# ge7.net
KiCad netlist of a schematic drawn in EAGLE
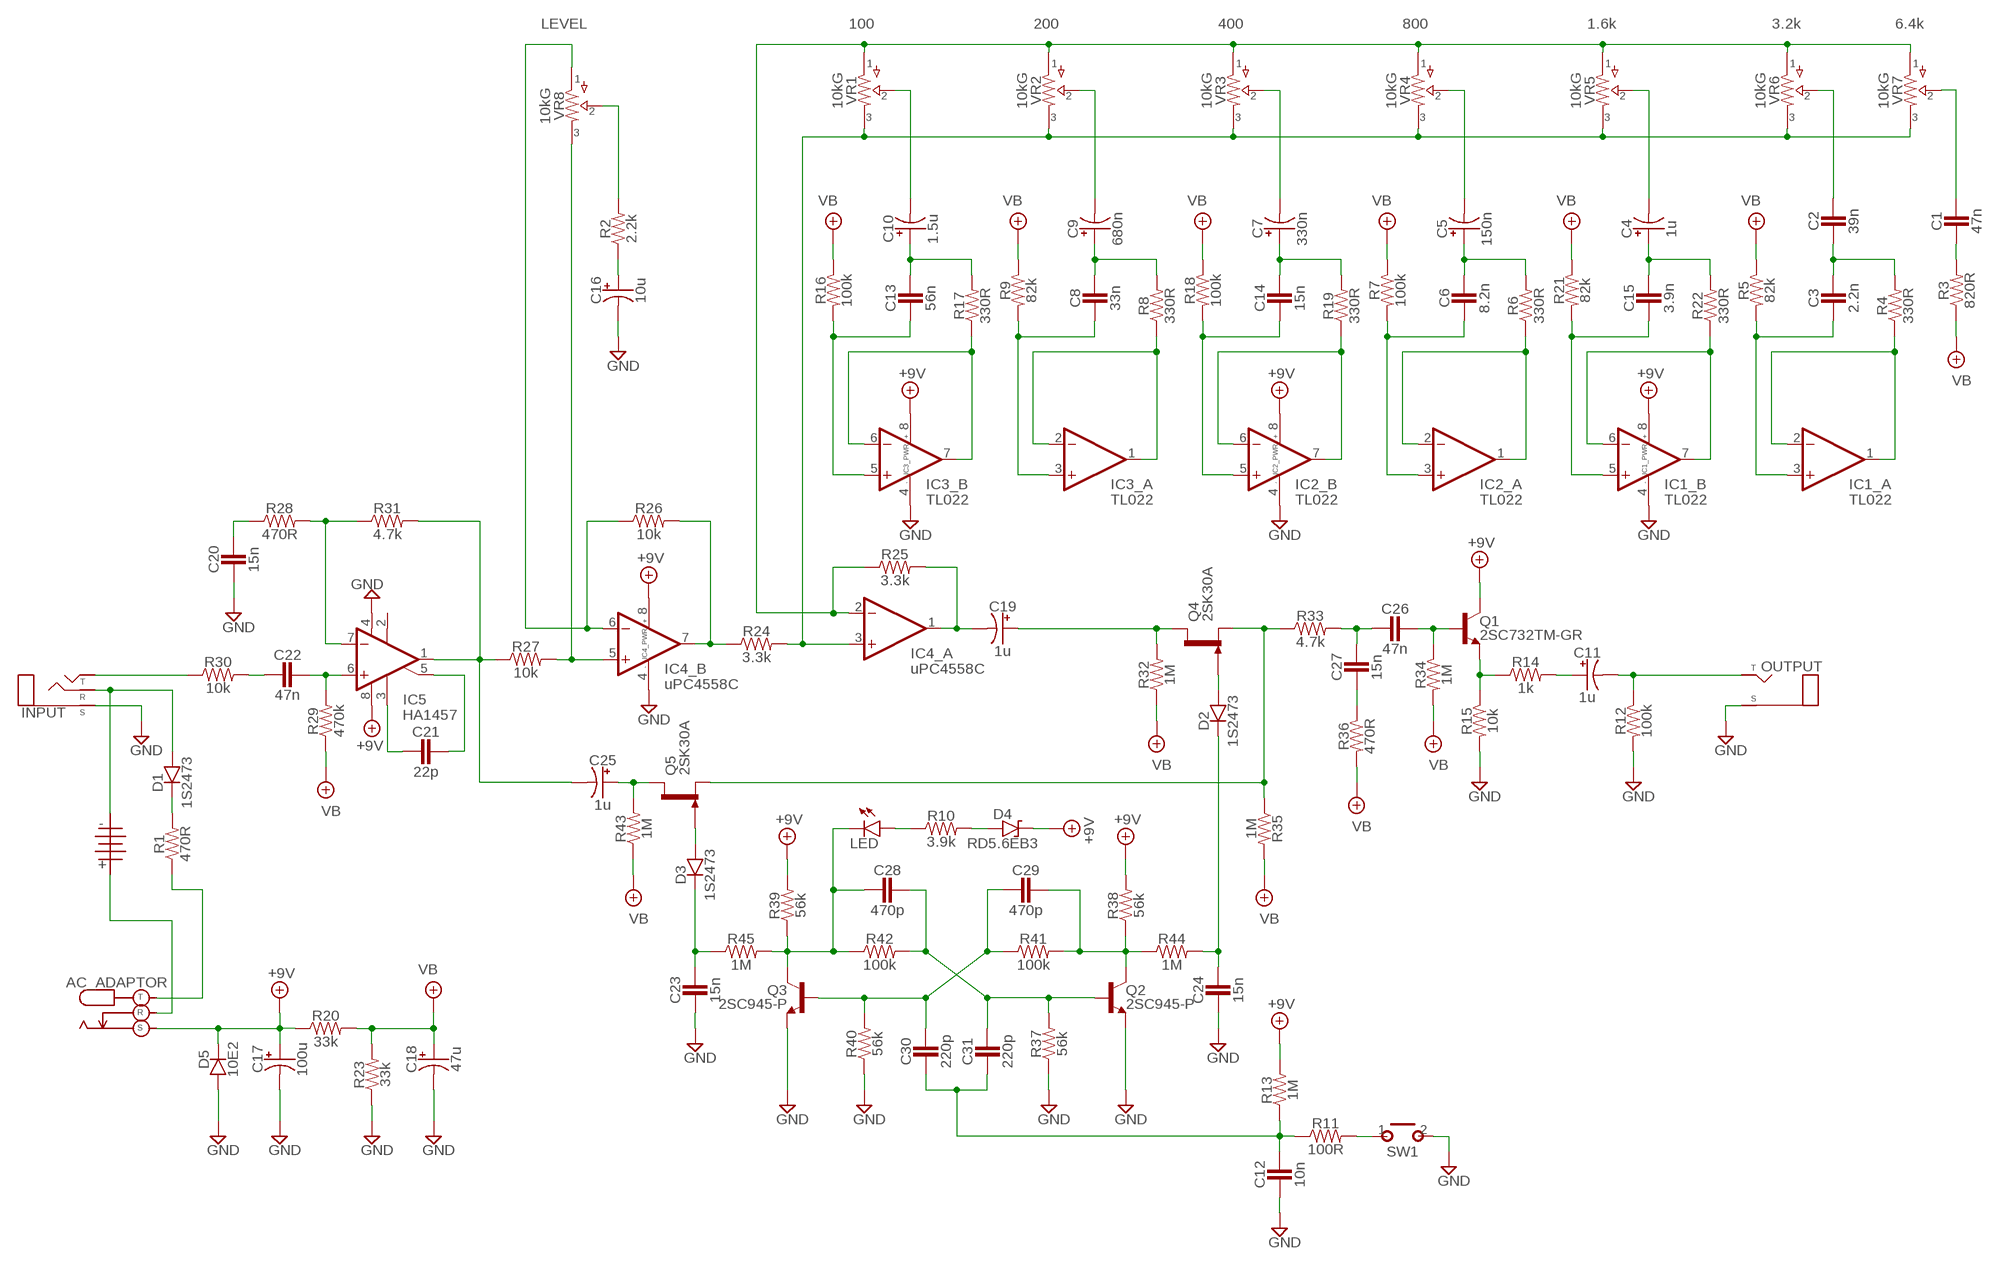
[diagram p0: schematic, sheet 1]

(export (version "E")
  (design (tool "Eeschema 10.0.6"))
  (components
    (comp (ref "AC_ADAPTOR")
      (value "DC_KOBICONN")
      (footprint "eagle-import:DC_KOBICONN")
      (libsource (lib "eagle-import") (part "DC_KOBICONN"))
    )
    (comp (ref "BATTERY")
      (value "BATTERY")
      (footprint "eagle-import:TWO_PADS")
      (libsource (lib "eagle-import") (part "BATTERY"))
    )
    (comp (ref "C1")
      (value "47n")
      (footprint "eagle-import:BOX_SMALL")
      (libsource (lib "eagle-import") (part "CER/FILMBOX.1"))
    )
    (comp (ref "C2")
      (value "39n")
      (footprint "eagle-import:BOX_SMALL")
      (libsource (lib "eagle-import") (part "CER/FILMBOX.1"))
    )
    (comp (ref "C3")
      (value "2.2n")
      (footprint "eagle-import:BOX_SMALL")
      (libsource (lib "eagle-import") (part "CER/FILMBOX.1"))
    )
    (comp (ref "C4")
      (value "1u")
      (footprint "eagle-import:040_020")
      (libsource (lib "eagle-import") (part "0400"))
    )
    (comp (ref "C5")
      (value "150n")
      (footprint "eagle-import:040_020")
      (libsource (lib "eagle-import") (part "0400"))
    )
    (comp (ref "C6")
      (value "8.2n")
      (footprint "eagle-import:BOX_SMALL")
      (libsource (lib "eagle-import") (part "CER/FILMBOX.1"))
    )
    (comp (ref "C7")
      (value "330n")
      (footprint "eagle-import:040_020")
      (libsource (lib "eagle-import") (part "0400"))
    )
    (comp (ref "C8")
      (value "33n")
      (footprint "eagle-import:BOX_SMALL")
      (libsource (lib "eagle-import") (part "CER/FILMBOX.1"))
    )
    (comp (ref "C9")
      (value "680n")
      (footprint "eagle-import:040_020")
      (libsource (lib "eagle-import") (part "0400"))
    )
    (comp (ref "C10")
      (value "1.5u")
      (footprint "eagle-import:040_020")
      (libsource (lib "eagle-import") (part "0400"))
    )
    (comp (ref "C11")
      (value "1u")
      (footprint "eagle-import:040_020")
      (libsource (lib "eagle-import") (part "0400"))
    )
    (comp (ref "C12")
      (value "10n")
      (footprint "eagle-import:BOX_SMALL")
      (libsource (lib "eagle-import") (part "CER/FILMBOX.1"))
    )
    (comp (ref "C13")
      (value "56n")
      (footprint "eagle-import:BOX_SMALL")
      (libsource (lib "eagle-import") (part "CER/FILMBOX.1"))
    )
    (comp (ref "C14")
      (value "15n")
      (footprint "eagle-import:BOX_SMALL")
      (libsource (lib "eagle-import") (part "CER/FILMBOX.1"))
    )
    (comp (ref "C15")
      (value "3.9n")
      (footprint "eagle-import:BOX_SMALL")
      (libsource (lib "eagle-import") (part "CER/FILMBOX.1"))
    )
    (comp (ref "C16")
      (value "10u")
      (footprint "eagle-import:040_020")
      (libsource (lib "eagle-import") (part "0400"))
    )
    (comp (ref "C17")
      (value "100u")
      (footprint "eagle-import:040_020")
      (libsource (lib "eagle-import") (part "0400"))
    )
    (comp (ref "C18")
      (value "47u")
      (footprint "eagle-import:040_020")
      (libsource (lib "eagle-import") (part "0400"))
    )
    (comp (ref "C19")
      (value "1u")
      (footprint "eagle-import:040_020")
      (libsource (lib "eagle-import") (part "0400"))
    )
    (comp (ref "C20")
      (value "15n")
      (footprint "eagle-import:BOX_SMALL")
      (libsource (lib "eagle-import") (part "CER/FILMBOX.1"))
    )
    (comp (ref "C21")
      (value "22p")
      (footprint "eagle-import:BOX_SMALL")
      (libsource (lib "eagle-import") (part "CER/FILMBOX.1"))
    )
    (comp (ref "C22")
      (value "47n")
      (footprint "eagle-import:BOX_SMALL")
      (libsource (lib "eagle-import") (part "CER/FILMBOX.1"))
    )
    (comp (ref "C23")
      (value "15n")
      (footprint "eagle-import:BOX_SMALL")
      (libsource (lib "eagle-import") (part "CER/FILMBOX.1"))
    )
    (comp (ref "C24")
      (value "15n")
      (footprint "eagle-import:BOX_SMALL")
      (libsource (lib "eagle-import") (part "CER/FILMBOX.1"))
    )
    (comp (ref "C25")
      (value "1u")
      (footprint "eagle-import:040_020")
      (libsource (lib "eagle-import") (part "0400"))
    )
    (comp (ref "C26")
      (value "47n")
      (footprint "eagle-import:BOX_SMALL")
      (libsource (lib "eagle-import") (part "CER/FILMBOX.1"))
    )
    (comp (ref "C27")
      (value "15n")
      (footprint "eagle-import:BOX_SMALL")
      (libsource (lib "eagle-import") (part "CER/FILMBOX.1"))
    )
    (comp (ref "C28")
      (value "470p")
      (footprint "eagle-import:BOX_SMALL")
      (libsource (lib "eagle-import") (part "CER/FILMBOX.1"))
    )
    (comp (ref "C29")
      (value "470p")
      (footprint "eagle-import:BOX_SMALL")
      (libsource (lib "eagle-import") (part "CER/FILMBOX.1"))
    )
    (comp (ref "C30")
      (value "220p")
      (footprint "eagle-import:BOX_SMALL")
      (libsource (lib "eagle-import") (part "CER/FILMBOX.1"))
    )
    (comp (ref "C31")
      (value "220p")
      (footprint "eagle-import:BOX_SMALL")
      (libsource (lib "eagle-import") (part "CER/FILMBOX.1"))
    )
    (comp (ref "D1")
      (value "1S2473")
      (footprint "eagle-import:DO35-2")
      (libsource (lib "eagle-import") (part "DO35.2"))
    )
    (comp (ref "D2")
      (value "1S2473")
      (footprint "eagle-import:DO35-2")
      (libsource (lib "eagle-import") (part "DO35.2"))
    )
    (comp (ref "D3")
      (value "1S2473")
      (footprint "eagle-import:DO35-2")
      (libsource (lib "eagle-import") (part "DO35.2"))
    )
    (comp (ref "D4")
      (value "RD5.6EB3")
      (footprint "eagle-import:DO41-2")
      (libsource (lib "eagle-import") (part "ZENER.2"))
    )
    (comp (ref "D5")
      (value "10E2")
      (footprint "eagle-import:DO35-2")
      (libsource (lib "eagle-import") (part "DO35.2"))
    )
    (comp (ref "IC1")
      (value "TL022")
      (footprint "eagle-import:DIL0")
      (libsource (lib "eagle-import") (part "DUALTH"))
    )
    (comp (ref "IC2")
      (value "TL022")
      (footprint "eagle-import:DIL0")
      (libsource (lib "eagle-import") (part "DUALTH"))
    )
    (comp (ref "IC3")
      (value "TL022")
      (footprint "eagle-import:DIL0")
      (libsource (lib "eagle-import") (part "DUALTH"))
    )
    (comp (ref "IC4")
      (value "uPC4558C")
      (footprint "eagle-import:DIL0")
      (libsource (lib "eagle-import") (part "DUALTH"))
    )
    (comp (ref "IC5")
      (value "HA1457")
      (footprint "eagle-import:SIL8")
      (libsource (lib "eagle-import") (part "HA1457"))
    )
    (comp (ref "INPUT")
      (value "STEREO3PADS")
      (footprint "eagle-import:THREEPADS")
      (libsource (lib "eagle-import") (part "STEREO3PADS"))
    )
    (comp (ref "LED")
      (value "LED")
      (footprint "eagle-import:3MM_D")
      (libsource (lib "eagle-import") (part "LED"))
    )
    (comp (ref "OUTPUT")
      (value "MONO")
      (footprint "eagle-import:TWO_PADS")
      (libsource (lib "eagle-import") (part "MONO"))
    )
    (comp (ref "Q1")
      (value "2SC732TM-GR")
      (footprint "eagle-import:TO92-")
      (libsource (lib "eagle-import") (part "2SC828A"))
    )
    (comp (ref "Q2")
      (value "2SC945-P")
      (footprint "eagle-import:TO92-")
      (libsource (lib "eagle-import") (part "2SC828A"))
    )
    (comp (ref "Q3")
      (value "2SC945-P")
      (footprint "eagle-import:TO92-")
      (libsource (lib "eagle-import") (part "2SC828A"))
    )
    (comp (ref "Q4")
      (value "2SK30A")
      (footprint "eagle-import:TO92-")
      (libsource (lib "eagle-import") (part "2N5457"))
    )
    (comp (ref "Q5")
      (value "2SK30A")
      (footprint "eagle-import:TO92-")
      (libsource (lib "eagle-import") (part "2N5457"))
    )
    (comp (ref "R1")
      (value "470R")
      (footprint "eagle-import:R0207_3")
      (libsource (lib "eagle-import") (part "R_.3B"))
    )
    (comp (ref "R2")
      (value "2.2k")
      (footprint "eagle-import:R0207_3")
      (libsource (lib "eagle-import") (part "R_.3B"))
    )
    (comp (ref "R3")
      (value "820R")
      (footprint "eagle-import:R0207_3")
      (libsource (lib "eagle-import") (part "R_.3B"))
    )
    (comp (ref "R4")
      (value "330R")
      (footprint "eagle-import:R0207_3")
      (libsource (lib "eagle-import") (part "R_.3B"))
    )
    (comp (ref "R5")
      (value "82k")
      (footprint "eagle-import:R0207_3")
      (libsource (lib "eagle-import") (part "R_.3B"))
    )
    (comp (ref "R6")
      (value "330R")
      (footprint "eagle-import:R0207_3")
      (libsource (lib "eagle-import") (part "R_.3B"))
    )
    (comp (ref "R7")
      (value "100k")
      (footprint "eagle-import:R0207_3")
      (libsource (lib "eagle-import") (part "R_.3B"))
    )
    (comp (ref "R8")
      (value "330R")
      (footprint "eagle-import:R0207_3")
      (libsource (lib "eagle-import") (part "R_.3B"))
    )
    (comp (ref "R9")
      (value "82k")
      (footprint "eagle-import:R0207_3")
      (libsource (lib "eagle-import") (part "R_.3B"))
    )
    (comp (ref "R10")
      (value "3.9k")
      (footprint "eagle-import:R0207_3")
      (libsource (lib "eagle-import") (part "R_.3B"))
    )
    (comp (ref "R11")
      (value "100R")
      (footprint "eagle-import:R0207_3")
      (libsource (lib "eagle-import") (part "R_.3B"))
    )
    (comp (ref "R12")
      (value "100k")
      (footprint "eagle-import:R0207_3")
      (libsource (lib "eagle-import") (part "R_.3B"))
    )
    (comp (ref "R13")
      (value "1M")
      (footprint "eagle-import:R0207_3")
      (libsource (lib "eagle-import") (part "R_.3B"))
    )
    (comp (ref "R14")
      (value "1k")
      (footprint "eagle-import:R0207_3")
      (libsource (lib "eagle-import") (part "R_.3B"))
    )
    (comp (ref "R15")
      (value "10k")
      (footprint "eagle-import:R0207_3")
      (libsource (lib "eagle-import") (part "R_.3B"))
    )
    (comp (ref "R16")
      (value "100k")
      (footprint "eagle-import:R0207_3")
      (libsource (lib "eagle-import") (part "R_.3B"))
    )
    (comp (ref "R17")
      (value "330R")
      (footprint "eagle-import:R0207_3")
      (libsource (lib "eagle-import") (part "R_.3B"))
    )
    (comp (ref "R18")
      (value "100k")
      (footprint "eagle-import:R0207_3")
      (libsource (lib "eagle-import") (part "R_.3B"))
    )
    (comp (ref "R19")
      (value "330R")
      (footprint "eagle-import:R0207_3")
      (libsource (lib "eagle-import") (part "R_.3B"))
    )
    (comp (ref "R20")
      (value "33k")
      (footprint "eagle-import:R0207_3")
      (libsource (lib "eagle-import") (part "R_.3B"))
    )
    (comp (ref "R21")
      (value "82k")
      (footprint "eagle-import:R0207_3")
      (libsource (lib "eagle-import") (part "R_.3B"))
    )
    (comp (ref "R22")
      (value "330R")
      (footprint "eagle-import:R0207_3")
      (libsource (lib "eagle-import") (part "R_.3B"))
    )
    (comp (ref "R23")
      (value "33k")
      (footprint "eagle-import:R0207_3")
      (libsource (lib "eagle-import") (part "R_.3B"))
    )
    (comp (ref "R24")
      (value "3.3k")
      (footprint "eagle-import:R0207_3")
      (libsource (lib "eagle-import") (part "R_.3B"))
    )
    (comp (ref "R25")
      (value "3.3k")
      (footprint "eagle-import:R0207_3")
      (libsource (lib "eagle-import") (part "R_.3B"))
    )
    (comp (ref "R26")
      (value "10k")
      (footprint "eagle-import:R0207_3")
      (libsource (lib "eagle-import") (part "R_.3B"))
    )
    (comp (ref "R27")
      (value "10k")
      (footprint "eagle-import:R0207_3")
      (libsource (lib "eagle-import") (part "R_.3B"))
    )
    (comp (ref "R28")
      (value "470R")
      (footprint "eagle-import:R0207_3")
      (libsource (lib "eagle-import") (part "R_.3B"))
    )
    (comp (ref "R29")
      (value "470k")
      (footprint "eagle-import:R0207_3")
      (libsource (lib "eagle-import") (part "R_.3B"))
    )
    (comp (ref "R30")
      (value "10k")
      (footprint "eagle-import:R0207_3")
      (libsource (lib "eagle-import") (part "R_.3B"))
    )
    (comp (ref "R31")
      (value "4.7k")
      (footprint "eagle-import:R0207_3")
      (libsource (lib "eagle-import") (part "R_.3B"))
    )
    (comp (ref "R32")
      (value "1M")
      (footprint "eagle-import:R0207_3")
      (libsource (lib "eagle-import") (part "R_.3B"))
    )
    (comp (ref "R33")
      (value "4.7k")
      (footprint "eagle-import:R0207_3")
      (libsource (lib "eagle-import") (part "R_.3B"))
    )
    (comp (ref "R34")
      (value "1M")
      (footprint "eagle-import:R0207_3")
      (libsource (lib "eagle-import") (part "R_.3B"))
    )
    (comp (ref "R35")
      (value "1M")
      (footprint "eagle-import:R0207_3")
      (libsource (lib "eagle-import") (part "R_.3B"))
    )
    (comp (ref "R36")
      (value "470R")
      (footprint "eagle-import:R0207_3")
      (libsource (lib "eagle-import") (part "R_.3B"))
    )
    (comp (ref "R37")
      (value "56k")
      (footprint "eagle-import:R0207_3")
      (libsource (lib "eagle-import") (part "R_.3B"))
    )
    (comp (ref "R38")
      (value "56k")
      (footprint "eagle-import:R0207_3")
      (libsource (lib "eagle-import") (part "R_.3B"))
    )
    (comp (ref "R39")
      (value "56k")
      (footprint "eagle-import:R0207_3")
      (libsource (lib "eagle-import") (part "R_.3B"))
    )
    (comp (ref "R40")
      (value "56k")
      (footprint "eagle-import:R0207_3")
      (libsource (lib "eagle-import") (part "R_.3B"))
    )
    (comp (ref "R41")
      (value "100k")
      (footprint "eagle-import:R0207_3")
      (libsource (lib "eagle-import") (part "R_.3B"))
    )
    (comp (ref "R42")
      (value "100k")
      (footprint "eagle-import:R0207_3")
      (libsource (lib "eagle-import") (part "R_.3B"))
    )
    (comp (ref "R43")
      (value "1M")
      (footprint "eagle-import:R0207_3")
      (libsource (lib "eagle-import") (part "R_.3B"))
    )
    (comp (ref "R44")
      (value "1M")
      (footprint "eagle-import:R0207_3")
      (libsource (lib "eagle-import") (part "R_.3B"))
    )
    (comp (ref "R45")
      (value "1M")
      (footprint "eagle-import:R0207_3")
      (libsource (lib "eagle-import") (part "R_.3B"))
    )
    (comp (ref "SW1")
      (value "MOMENTARY")
      (footprint "eagle-import:SPST")
      (libsource (lib "eagle-import") (part "MOMENTARY"))
    )
    (comp (ref "VR1")
      (value "10kG")
      (footprint "eagle-import:16MM")
      (libsource (lib "eagle-import") (part "POTS16MM"))
    )
    (comp (ref "VR2")
      (value "10kG")
      (footprint "eagle-import:16MM")
      (libsource (lib "eagle-import") (part "POTS16MM"))
    )
    (comp (ref "VR3")
      (value "10kG")
      (footprint "eagle-import:16MM")
      (libsource (lib "eagle-import") (part "POTS16MM"))
    )
    (comp (ref "VR4")
      (value "10kG")
      (footprint "eagle-import:16MM")
      (libsource (lib "eagle-import") (part "POTS16MM"))
    )
    (comp (ref "VR5")
      (value "10kG")
      (footprint "eagle-import:16MM")
      (libsource (lib "eagle-import") (part "POTS16MM"))
    )
    (comp (ref "VR6")
      (value "10kG")
      (footprint "eagle-import:16MM")
      (libsource (lib "eagle-import") (part "POTS16MM"))
    )
    (comp (ref "VR7")
      (value "10kG")
      (footprint "eagle-import:16MM")
      (libsource (lib "eagle-import") (part "POTS16MM"))
    )
    (comp (ref "VR8")
      (value "10kG")
      (footprint "eagle-import:16MM")
      (libsource (lib "eagle-import") (part "POTS16MM"))
    )
  )
  (nets
    (net (code "1") (name "+9V") (class "Default")
      (node (ref "AC_ADAPTOR") (pin "S") (pinfunction "S_S") (pintype "bidirectional"))
      (node (ref "C17") (pin "+") (pinfunction "+_+") (pintype "passive"))
      (node (ref "D4") (pin "C") (pinfunction "C_C") (pintype "passive"))
      (node (ref "D5") (pin "C") (pinfunction "C_C") (pintype "passive"))
      (node (ref "IC1") (pin "8") (pinfunction "V+_8") (pintype "power_in"))
      (node (ref "IC2") (pin "8") (pinfunction "V+_8") (pintype "power_in"))
      (node (ref "IC3") (pin "8") (pinfunction "V+_8") (pintype "power_in"))
      (node (ref "IC4") (pin "8") (pinfunction "V+_8") (pintype "power_in"))
      (node (ref "IC5") (pin "8") (pinfunction "V+_8") (pintype "power_in"))
      (node (ref "Q1") (pin "2") (pinfunction "C_2") (pintype "passive"))
      (node (ref "R13") (pin "2") (pinfunction "2_2") (pintype "passive"))
      (node (ref "R20") (pin "1") (pinfunction "1_1") (pintype "passive"))
      (node (ref "R38") (pin "2") (pinfunction "2_2") (pintype "passive"))
      (node (ref "R39") (pin "2") (pinfunction "2_2") (pintype "passive"))
    )
    (net (code "2") (name "GND") (class "Default")
      (node (ref "C12") (pin "2") (pinfunction "2_2") (pintype "passive"))
      (node (ref "C16") (pin "-") (pinfunction "-_-") (pintype "passive"))
      (node (ref "C17") (pin "-") (pinfunction "-_-") (pintype "passive"))
      (node (ref "C18") (pin "-") (pinfunction "-_-") (pintype "passive"))
      (node (ref "C20") (pin "2") (pinfunction "2_2") (pintype "passive"))
      (node (ref "C23") (pin "2") (pinfunction "2_2") (pintype "passive"))
      (node (ref "C24") (pin "2") (pinfunction "2_2") (pintype "passive"))
      (node (ref "D5") (pin "A") (pinfunction "A_A") (pintype "passive"))
      (node (ref "IC1") (pin "4") (pinfunction "V-_4") (pintype "power_in"))
      (node (ref "IC2") (pin "4") (pinfunction "V-_4") (pintype "power_in"))
      (node (ref "IC3") (pin "4") (pinfunction "V-_4") (pintype "power_in"))
      (node (ref "IC4") (pin "4") (pinfunction "V-_4") (pintype "power_in"))
      (node (ref "IC5") (pin "4") (pinfunction "V-_4") (pintype "power_in"))
      (node (ref "INPUT") (pin "SLEEVE") (pinfunction "S_SLEEVE") (pintype "passive"))
      (node (ref "OUTPUT") (pin "S") (pinfunction "SLEEVE_S") (pintype "passive"))
      (node (ref "Q2") (pin "3") (pinfunction "E_3") (pintype "passive"))
      (node (ref "Q3") (pin "3") (pinfunction "E_3") (pintype "passive"))
      (node (ref "R12") (pin "2") (pinfunction "2_2") (pintype "passive"))
      (node (ref "R15") (pin "2") (pinfunction "2_2") (pintype "passive"))
      (node (ref "R23") (pin "1") (pinfunction "1_1") (pintype "passive"))
      (node (ref "R37") (pin "1") (pinfunction "1_1") (pintype "passive"))
      (node (ref "R40") (pin "1") (pinfunction "1_1") (pintype "passive"))
      (node (ref "SW1") (pin "2") (pinfunction "S_2") (pintype "passive"))
    )
    (net (code "3") (name "Net-(AC_ADAPTOR-PadT)") (class "Default")
      (node (ref "AC_ADAPTOR") (pin "T") (pinfunction "T_T") (pintype "bidirectional"))
      (node (ref "R1") (pin "1") (pinfunction "1_1") (pintype "passive"))
    )
    (net (code "4") (name "Net-(BATTERY-P$1)") (class "Default")
      (node (ref "AC_ADAPTOR") (pin "R") (pinfunction "R_R") (pintype "bidirectional"))
      (node (ref "BATTERY") (pin "T") (pinfunction "P$1_T") (pintype "bidirectional"))
    )
    (net (code "5") (name "Net-(BATTERY-P$2)") (class "Default")
      (node (ref "BATTERY") (pin "S") (pinfunction "P$2_S") (pintype "bidirectional"))
      (node (ref "D1") (pin "A") (pinfunction "A_A") (pintype "passive"))
      (node (ref "INPUT") (pin "RING") (pinfunction "R_RING") (pintype "passive"))
    )
    (net (code "6") (name "Net-(C1-Pad1)") (class "Default")
      (node (ref "C1") (pin "1") (pinfunction "1_1") (pintype "passive"))
      (node (ref "VR7") (pin "2") (pinfunction "2_2") (pintype "passive"))
    )
    (net (code "7") (name "Net-(C1-Pad2)") (class "Default")
      (node (ref "C1") (pin "2") (pinfunction "2_2") (pintype "passive"))
      (node (ref "R3") (pin "2") (pinfunction "2_2") (pintype "passive"))
    )
    (net (code "8") (name "Net-(C2-Pad1)") (class "Default")
      (node (ref "C2") (pin "1") (pinfunction "1_1") (pintype "passive"))
      (node (ref "VR6") (pin "2") (pinfunction "2_2") (pintype "passive"))
    )
    (net (code "9") (name "Net-(C2-Pad2)") (class "Default")
      (node (ref "C2") (pin "2") (pinfunction "2_2") (pintype "passive"))
      (node (ref "C3") (pin "1") (pinfunction "1_1") (pintype "passive"))
      (node (ref "R4") (pin "2") (pinfunction "2_2") (pintype "passive"))
    )
    (net (code "10") (name "Net-(C4-Pad-)") (class "Default")
      (node (ref "C4") (pin "-") (pinfunction "-_-") (pintype "passive"))
      (node (ref "VR5") (pin "2") (pinfunction "2_2") (pintype "passive"))
    )
    (net (code "11") (name "Net-(C5-Pad+)") (class "Default")
      (node (ref "C5") (pin "+") (pinfunction "+_+") (pintype "passive"))
      (node (ref "C6") (pin "1") (pinfunction "1_1") (pintype "passive"))
      (node (ref "R6") (pin "2") (pinfunction "2_2") (pintype "passive"))
    )
    (net (code "12") (name "Net-(C5-Pad-)") (class "Default")
      (node (ref "C5") (pin "-") (pinfunction "-_-") (pintype "passive"))
      (node (ref "VR4") (pin "2") (pinfunction "2_2") (pintype "passive"))
    )
    (net (code "13") (name "Net-(C7-Pad-)") (class "Default")
      (node (ref "C7") (pin "-") (pinfunction "-_-") (pintype "passive"))
      (node (ref "VR3") (pin "2") (pinfunction "2_2") (pintype "passive"))
    )
    (net (code "14") (name "Net-(C8-Pad1)") (class "Default")
      (node (ref "C8") (pin "1") (pinfunction "1_1") (pintype "passive"))
      (node (ref "C9") (pin "+") (pinfunction "+_+") (pintype "passive"))
      (node (ref "R8") (pin "2") (pinfunction "2_2") (pintype "passive"))
    )
    (net (code "15") (name "Net-(C9-Pad-)") (class "Default")
      (node (ref "C9") (pin "-") (pinfunction "-_-") (pintype "passive"))
      (node (ref "VR2") (pin "2") (pinfunction "2_2") (pintype "passive"))
    )
    (net (code "16") (name "Net-(C10-Pad+)") (class "Default")
      (node (ref "C10") (pin "+") (pinfunction "+_+") (pintype "passive"))
      (node (ref "C13") (pin "1") (pinfunction "1_1") (pintype "passive"))
      (node (ref "R17") (pin "2") (pinfunction "2_2") (pintype "passive"))
    )
    (net (code "17") (name "Net-(C10-Pad-)") (class "Default")
      (node (ref "C10") (pin "-") (pinfunction "-_-") (pintype "passive"))
      (node (ref "VR1") (pin "2") (pinfunction "2_2") (pintype "passive"))
    )
    (net (code "18") (name "Net-(C11-Pad+)") (class "Default")
      (node (ref "C11") (pin "+") (pinfunction "+_+") (pintype "passive"))
      (node (ref "R14") (pin "2") (pinfunction "2_2") (pintype "passive"))
    )
    (net (code "19") (name "Net-(C12-Pad1)") (class "Default")
      (node (ref "C12") (pin "1") (pinfunction "1_1") (pintype "passive"))
      (node (ref "C30") (pin "2") (pinfunction "2_2") (pintype "passive"))
      (node (ref "C31") (pin "2") (pinfunction "2_2") (pintype "passive"))
      (node (ref "R11") (pin "1") (pinfunction "1_1") (pintype "passive"))
      (node (ref "R13") (pin "1") (pinfunction "1_1") (pintype "passive"))
    )
    (net (code "20") (name "Net-(C14-Pad1)") (class "Default")
      (node (ref "C14") (pin "1") (pinfunction "1_1") (pintype "passive"))
      (node (ref "C7") (pin "+") (pinfunction "+_+") (pintype "passive"))
      (node (ref "R19") (pin "2") (pinfunction "2_2") (pintype "passive"))
    )
    (net (code "21") (name "Net-(C15-Pad1)") (class "Default")
      (node (ref "C15") (pin "1") (pinfunction "1_1") (pintype "passive"))
      (node (ref "C4") (pin "+") (pinfunction "+_+") (pintype "passive"))
      (node (ref "R22") (pin "2") (pinfunction "2_2") (pintype "passive"))
    )
    (net (code "22") (name "Net-(C16-Pad+)") (class "Default")
      (node (ref "C16") (pin "+") (pinfunction "+_+") (pintype "passive"))
      (node (ref "R2") (pin "1") (pinfunction "1_1") (pintype "passive"))
    )
    (net (code "23") (name "Net-(C20-Pad1)") (class "Default")
      (node (ref "C20") (pin "1") (pinfunction "1_1") (pintype "passive"))
      (node (ref "R28") (pin "1") (pinfunction "1_1") (pintype "passive"))
    )
    (net (code "24") (name "Net-(C22-Pad2)") (class "Default")
      (node (ref "C22") (pin "2") (pinfunction "2_2") (pintype "passive"))
      (node (ref "R30") (pin "2") (pinfunction "2_2") (pintype "passive"))
    )
    (net (code "25") (name "Net-(C23-Pad1)") (class "Default")
      (node (ref "C23") (pin "1") (pinfunction "1_1") (pintype "passive"))
      (node (ref "D3") (pin "C") (pinfunction "C_C") (pintype "passive"))
      (node (ref "R45") (pin "1") (pinfunction "1_1") (pintype "passive"))
    )
    (net (code "26") (name "Net-(C24-Pad1)") (class "Default")
      (node (ref "C24") (pin "1") (pinfunction "1_1") (pintype "passive"))
      (node (ref "D2") (pin "C") (pinfunction "C_C") (pintype "passive"))
      (node (ref "R44") (pin "2") (pinfunction "2_2") (pintype "passive"))
    )
    (net (code "27") (name "Net-(C26-Pad2)") (class "Default")
      (node (ref "C26") (pin "2") (pinfunction "2_2") (pintype "passive"))
      (node (ref "C27") (pin "1") (pinfunction "1_1") (pintype "passive"))
      (node (ref "R33") (pin "2") (pinfunction "2_2") (pintype "passive"))
    )
    (net (code "28") (name "Net-(C27-Pad2)") (class "Default")
      (node (ref "C27") (pin "2") (pinfunction "2_2") (pintype "passive"))
      (node (ref "R36") (pin "1") (pinfunction "1_1") (pintype "passive"))
    )
    (net (code "29") (name "Net-(D1-PadC)") (class "Default")
      (node (ref "D1") (pin "C") (pinfunction "C_C") (pintype "passive"))
      (node (ref "R1") (pin "2") (pinfunction "2_2") (pintype "passive"))
    )
    (net (code "30") (name "Net-(D4-PadA)") (class "Default")
      (node (ref "D4") (pin "A") (pinfunction "A_A") (pintype "passive"))
      (node (ref "R10") (pin "2") (pinfunction "2_2") (pintype "passive"))
    )
    (net (code "31") (name "Net-(IC1A-+IN)") (class "Default")
      (node (ref "C3") (pin "2") (pinfunction "2_2") (pintype "passive"))
      (node (ref "IC1") (pin "3") (pinfunction "+IN_3") (pintype "input"))
      (node (ref "R5") (pin "2") (pinfunction "2_2") (pintype "passive"))
    )
    (net (code "32") (name "Net-(IC1A--IN)") (class "Default")
      (node (ref "IC1") (pin "1") (pinfunction "OUT_1") (pintype "output"))
      (node (ref "IC1") (pin "2") (pinfunction "-IN_2") (pintype "input"))
      (node (ref "R4") (pin "1") (pinfunction "1_1") (pintype "passive"))
    )
    (net (code "33") (name "Net-(IC1B-+IN)") (class "Default")
      (node (ref "C15") (pin "2") (pinfunction "2_2") (pintype "passive"))
      (node (ref "IC1") (pin "5") (pinfunction "+IN_5") (pintype "input"))
      (node (ref "R21") (pin "2") (pinfunction "2_2") (pintype "passive"))
    )
    (net (code "34") (name "Net-(IC1B--IN)") (class "Default")
      (node (ref "IC1") (pin "6") (pinfunction "-IN_6") (pintype "input"))
      (node (ref "IC1") (pin "7") (pinfunction "OUT_7") (pintype "output"))
      (node (ref "R22") (pin "1") (pinfunction "1_1") (pintype "passive"))
    )
    (net (code "35") (name "Net-(IC2A-+IN)") (class "Default")
      (node (ref "C6") (pin "2") (pinfunction "2_2") (pintype "passive"))
      (node (ref "IC2") (pin "3") (pinfunction "+IN_3") (pintype "input"))
      (node (ref "R7") (pin "2") (pinfunction "2_2") (pintype "passive"))
    )
    (net (code "36") (name "Net-(IC2A--IN)") (class "Default")
      (node (ref "IC2") (pin "1") (pinfunction "OUT_1") (pintype "output"))
      (node (ref "IC2") (pin "2") (pinfunction "-IN_2") (pintype "input"))
      (node (ref "R6") (pin "1") (pinfunction "1_1") (pintype "passive"))
    )
    (net (code "37") (name "Net-(IC2B-+IN)") (class "Default")
      (node (ref "C14") (pin "2") (pinfunction "2_2") (pintype "passive"))
      (node (ref "IC2") (pin "5") (pinfunction "+IN_5") (pintype "input"))
      (node (ref "R18") (pin "2") (pinfunction "2_2") (pintype "passive"))
    )
    (net (code "38") (name "Net-(IC2B--IN)") (class "Default")
      (node (ref "IC2") (pin "6") (pinfunction "-IN_6") (pintype "input"))
      (node (ref "IC2") (pin "7") (pinfunction "OUT_7") (pintype "output"))
      (node (ref "R19") (pin "1") (pinfunction "1_1") (pintype "passive"))
    )
    (net (code "39") (name "Net-(IC3A-+IN)") (class "Default")
      (node (ref "C8") (pin "2") (pinfunction "2_2") (pintype "passive"))
      (node (ref "IC3") (pin "3") (pinfunction "+IN_3") (pintype "input"))
      (node (ref "R9") (pin "2") (pinfunction "2_2") (pintype "passive"))
    )
    (net (code "40") (name "Net-(IC3A--IN)") (class "Default")
      (node (ref "IC3") (pin "1") (pinfunction "OUT_1") (pintype "output"))
      (node (ref "IC3") (pin "2") (pinfunction "-IN_2") (pintype "input"))
      (node (ref "R8") (pin "1") (pinfunction "1_1") (pintype "passive"))
    )
    (net (code "41") (name "Net-(IC3B-+IN)") (class "Default")
      (node (ref "C13") (pin "2") (pinfunction "2_2") (pintype "passive"))
      (node (ref "IC3") (pin "5") (pinfunction "+IN_5") (pintype "input"))
      (node (ref "R16") (pin "2") (pinfunction "2_2") (pintype "passive"))
    )
    (net (code "42") (name "Net-(IC3B--IN)") (class "Default")
      (node (ref "IC3") (pin "6") (pinfunction "-IN_6") (pintype "input"))
      (node (ref "IC3") (pin "7") (pinfunction "OUT_7") (pintype "output"))
      (node (ref "R17") (pin "1") (pinfunction "1_1") (pintype "passive"))
    )
    (net (code "43") (name "Net-(IC4A-+IN)") (class "Default")
      (node (ref "IC4") (pin "3") (pinfunction "+IN_3") (pintype "input"))
      (node (ref "R24") (pin "2") (pinfunction "2_2") (pintype "passive"))
      (node (ref "VR1") (pin "3") (pinfunction "3_3") (pintype "passive"))
      (node (ref "VR2") (pin "3") (pinfunction "3_3") (pintype "passive"))
      (node (ref "VR3") (pin "3") (pinfunction "3_3") (pintype "passive"))
      (node (ref "VR4") (pin "3") (pinfunction "3_3") (pintype "passive"))
      (node (ref "VR5") (pin "3") (pinfunction "3_3") (pintype "passive"))
      (node (ref "VR6") (pin "3") (pinfunction "3_3") (pintype "passive"))
      (node (ref "VR7") (pin "3") (pinfunction "3_3") (pintype "passive"))
    )
    (net (code "44") (name "Net-(IC4A--IN)") (class "Default")
      (node (ref "IC4") (pin "2") (pinfunction "-IN_2") (pintype "input"))
      (node (ref "R25") (pin "1") (pinfunction "1_1") (pintype "passive"))
      (node (ref "VR1") (pin "1") (pinfunction "1_1") (pintype "passive"))
      (node (ref "VR2") (pin "1") (pinfunction "1_1") (pintype "passive"))
      (node (ref "VR3") (pin "1") (pinfunction "1_1") (pintype "passive"))
      (node (ref "VR4") (pin "1") (pinfunction "1_1") (pintype "passive"))
      (node (ref "VR5") (pin "1") (pinfunction "1_1") (pintype "passive"))
      (node (ref "VR6") (pin "1") (pinfunction "1_1") (pintype "passive"))
      (node (ref "VR7") (pin "1") (pinfunction "1_1") (pintype "passive"))
    )
    (net (code "45") (name "Net-(IC4A-OUT)") (class "Default")
      (node (ref "C19") (pin "-") (pinfunction "-_-") (pintype "passive"))
      (node (ref "IC4") (pin "1") (pinfunction "OUT_1") (pintype "output"))
      (node (ref "R25") (pin "2") (pinfunction "2_2") (pintype "passive"))
    )
    (net (code "46") (name "Net-(IC4B-+IN)") (class "Default")
      (node (ref "IC4") (pin "5") (pinfunction "+IN_5") (pintype "input"))
      (node (ref "R27") (pin "2") (pinfunction "2_2") (pintype "passive"))
      (node (ref "VR8") (pin "3") (pinfunction "3_3") (pintype "passive"))
    )
    (net (code "47") (name "Net-(IC4B--IN)") (class "Default")
      (node (ref "IC4") (pin "6") (pinfunction "-IN_6") (pintype "input"))
      (node (ref "R26") (pin "1") (pinfunction "1_1") (pintype "passive"))
      (node (ref "VR8") (pin "1") (pinfunction "1_1") (pintype "passive"))
    )
    (net (code "48") (name "Net-(IC4B-OUT)") (class "Default")
      (node (ref "IC4") (pin "7") (pinfunction "OUT_7") (pintype "output"))
      (node (ref "R24") (pin "1") (pinfunction "1_1") (pintype "passive"))
      (node (ref "R26") (pin "2") (pinfunction "2_2") (pintype "passive"))
    )
    (net (code "49") (name "Net-(IC5-+IN)") (class "Default")
      (node (ref "C22") (pin "1") (pinfunction "1_1") (pintype "passive"))
      (node (ref "IC5") (pin "6") (pinfunction "+IN_6") (pintype "input"))
      (node (ref "R29") (pin "2") (pinfunction "2_2") (pintype "passive"))
    )
    (net (code "50") (name "Net-(IC5--IN)") (class "Default")
      (node (ref "IC5") (pin "7") (pinfunction "-IN_7") (pintype "input"))
      (node (ref "R28") (pin "2") (pinfunction "2_2") (pintype "passive"))
      (node (ref "R31") (pin "1") (pinfunction "1_1") (pintype "passive"))
    )
    (net (code "51") (name "Net-(IC5-ON1)") (class "Default")
      (node (ref "C21") (pin "2") (pinfunction "2_2") (pintype "passive"))
      (node (ref "IC5") (pin "3") (pinfunction "ON1_3") (pintype "passive"))
    )
    (net (code "52") (name "Net-(IC5-ON2)") (class "Default")
      (node (ref "C21") (pin "1") (pinfunction "1_1") (pintype "passive"))
      (node (ref "IC5") (pin "5") (pinfunction "ON2_5") (pintype "passive"))
    )
    (net (code "53") (name "Net-(IC5-OUT)") (class "Default")
      (node (ref "C25") (pin "-") (pinfunction "-_-") (pintype "passive"))
      (node (ref "IC5") (pin "1") (pinfunction "OUT_1") (pintype "output"))
      (node (ref "R27") (pin "1") (pinfunction "1_1") (pintype "passive"))
      (node (ref "R31") (pin "2") (pinfunction "2_2") (pintype "passive"))
    )
    (net (code "54") (name "Net-(INPUT-T)") (class "Default")
      (node (ref "INPUT") (pin "TIP") (pinfunction "T_TIP") (pintype "passive"))
      (node (ref "R30") (pin "1") (pinfunction "1_1") (pintype "passive"))
    )
    (net (code "55") (name "Net-(LED-A)") (class "Default")
      (node (ref "LED") (pin "ANODE") (pinfunction "A_ANODE") (pintype "passive"))
      (node (ref "R10") (pin "1") (pinfunction "1_1") (pintype "passive"))
    )
    (net (code "56") (name "Net-(LED-C)") (class "Default")
      (node (ref "C28") (pin "2") (pinfunction "2_2") (pintype "passive"))
      (node (ref "LED") (pin "P$1") (pinfunction "C_P$1") (pintype "passive"))
      (node (ref "Q3") (pin "2") (pinfunction "C_2") (pintype "passive"))
      (node (ref "R39") (pin "1") (pinfunction "1_1") (pintype "passive"))
      (node (ref "R42") (pin "1") (pinfunction "1_1") (pintype "passive"))
      (node (ref "R45") (pin "2") (pinfunction "2_2") (pintype "passive"))
    )
    (net (code "57") (name "Net-(OUTPUT-TIP)") (class "Default")
      (node (ref "C11") (pin "-") (pinfunction "-_-") (pintype "passive"))
      (node (ref "OUTPUT") (pin "T") (pinfunction "TIP_T") (pintype "passive"))
      (node (ref "R12") (pin "1") (pinfunction "1_1") (pintype "passive"))
    )
    (net (code "58") (name "Net-(Q1-B)") (class "Default")
      (node (ref "C26") (pin "1") (pinfunction "1_1") (pintype "passive"))
      (node (ref "Q1") (pin "1") (pinfunction "B_1") (pintype "passive"))
      (node (ref "R34") (pin "1") (pinfunction "1_1") (pintype "passive"))
    )
    (net (code "59") (name "Net-(Q1-E)") (class "Default")
      (node (ref "Q1") (pin "3") (pinfunction "E_3") (pintype "passive"))
      (node (ref "R14") (pin "1") (pinfunction "1_1") (pintype "passive"))
      (node (ref "R15") (pin "1") (pinfunction "1_1") (pintype "passive"))
    )
    (net (code "60") (name "Net-(Q2-B)") (class "Default")
      (node (ref "C28") (pin "1") (pinfunction "1_1") (pintype "passive"))
      (node (ref "C31") (pin "1") (pinfunction "1_1") (pintype "passive"))
      (node (ref "Q2") (pin "1") (pinfunction "B_1") (pintype "passive"))
      (node (ref "R37") (pin "2") (pinfunction "2_2") (pintype "passive"))
      (node (ref "R42") (pin "2") (pinfunction "2_2") (pintype "passive"))
    )
    (net (code "61") (name "Net-(Q2-C)") (class "Default")
      (node (ref "C29") (pin "1") (pinfunction "1_1") (pintype "passive"))
      (node (ref "Q2") (pin "2") (pinfunction "C_2") (pintype "passive"))
      (node (ref "R38") (pin "1") (pinfunction "1_1") (pintype "passive"))
      (node (ref "R41") (pin "2") (pinfunction "2_2") (pintype "passive"))
      (node (ref "R44") (pin "1") (pinfunction "1_1") (pintype "passive"))
    )
    (net (code "62") (name "Net-(Q3-B)") (class "Default")
      (node (ref "C29") (pin "2") (pinfunction "2_2") (pintype "passive"))
      (node (ref "C30") (pin "1") (pinfunction "1_1") (pintype "passive"))
      (node (ref "Q3") (pin "1") (pinfunction "B_1") (pintype "passive"))
      (node (ref "R40") (pin "2") (pinfunction "2_2") (pintype "passive"))
      (node (ref "R41") (pin "1") (pinfunction "1_1") (pintype "passive"))
    )
    (net (code "63") (name "Net-(Q4-D)") (class "Default")
      (node (ref "C19") (pin "+") (pinfunction "+_+") (pintype "passive"))
      (node (ref "Q4") (pin "3") (pinfunction "D_3") (pintype "passive"))
      (node (ref "R32") (pin "2") (pinfunction "2_2") (pintype "passive"))
    )
    (net (code "64") (name "Net-(Q4-G)") (class "Default")
      (node (ref "D2") (pin "A") (pinfunction "A_A") (pintype "passive"))
      (node (ref "Q4") (pin "1") (pinfunction "G_1") (pintype "passive"))
    )
    (net (code "65") (name "Net-(Q4-S)") (class "Default")
      (node (ref "Q4") (pin "2") (pinfunction "S_2") (pintype "passive"))
      (node (ref "Q5") (pin "2") (pinfunction "S_2") (pintype "passive"))
      (node (ref "R33") (pin "1") (pinfunction "1_1") (pintype "passive"))
      (node (ref "R35") (pin "1") (pinfunction "1_1") (pintype "passive"))
    )
    (net (code "66") (name "Net-(Q5-D)") (class "Default")
      (node (ref "C25") (pin "+") (pinfunction "+_+") (pintype "passive"))
      (node (ref "Q5") (pin "3") (pinfunction "D_3") (pintype "passive"))
      (node (ref "R43") (pin "2") (pinfunction "2_2") (pintype "passive"))
    )
    (net (code "67") (name "Net-(Q5-G)") (class "Default")
      (node (ref "D3") (pin "A") (pinfunction "A_A") (pintype "passive"))
      (node (ref "Q5") (pin "1") (pinfunction "G_1") (pintype "passive"))
    )
    (net (code "68") (name "Net-(R2-Pad2)") (class "Default")
      (node (ref "R2") (pin "2") (pinfunction "2_2") (pintype "passive"))
      (node (ref "VR8") (pin "2") (pinfunction "2_2") (pintype "passive"))
    )
    (net (code "69") (name "Net-(SW1-P)") (class "Default")
      (node (ref "R11") (pin "2") (pinfunction "2_2") (pintype "passive"))
      (node (ref "SW1") (pin "1") (pinfunction "P_1") (pintype "passive"))
    )
    (net (code "70") (name "VB") (class "Default")
      (node (ref "C18") (pin "+") (pinfunction "+_+") (pintype "passive"))
      (node (ref "R16") (pin "1") (pinfunction "1_1") (pintype "passive"))
      (node (ref "R18") (pin "1") (pinfunction "1_1") (pintype "passive"))
      (node (ref "R20") (pin "2") (pinfunction "2_2") (pintype "passive"))
      (node (ref "R21") (pin "1") (pinfunction "1_1") (pintype "passive"))
      (node (ref "R23") (pin "2") (pinfunction "2_2") (pintype "passive"))
      (node (ref "R29") (pin "1") (pinfunction "1_1") (pintype "passive"))
      (node (ref "R3") (pin "1") (pinfunction "1_1") (pintype "passive"))
      (node (ref "R32") (pin "1") (pinfunction "1_1") (pintype "passive"))
      (node (ref "R34") (pin "2") (pinfunction "2_2") (pintype "passive"))
      (node (ref "R35") (pin "2") (pinfunction "2_2") (pintype "passive"))
      (node (ref "R36") (pin "2") (pinfunction "2_2") (pintype "passive"))
      (node (ref "R43") (pin "1") (pinfunction "1_1") (pintype "passive"))
      (node (ref "R5") (pin "1") (pinfunction "1_1") (pintype "passive"))
      (node (ref "R7") (pin "1") (pinfunction "1_1") (pintype "passive"))
      (node (ref "R9") (pin "1") (pinfunction "1_1") (pintype "passive"))
    )
    (net (code "71") (name "unconnected-(IC5-OPT-Pad2)") (class "Default")
      (node (ref "IC5") (pin "2") (pinfunction "OPT_2") (pintype "passive"))
    )
  )
)
